# Schematic.net
KiCad netlist of a schematic drawn in EAGLE
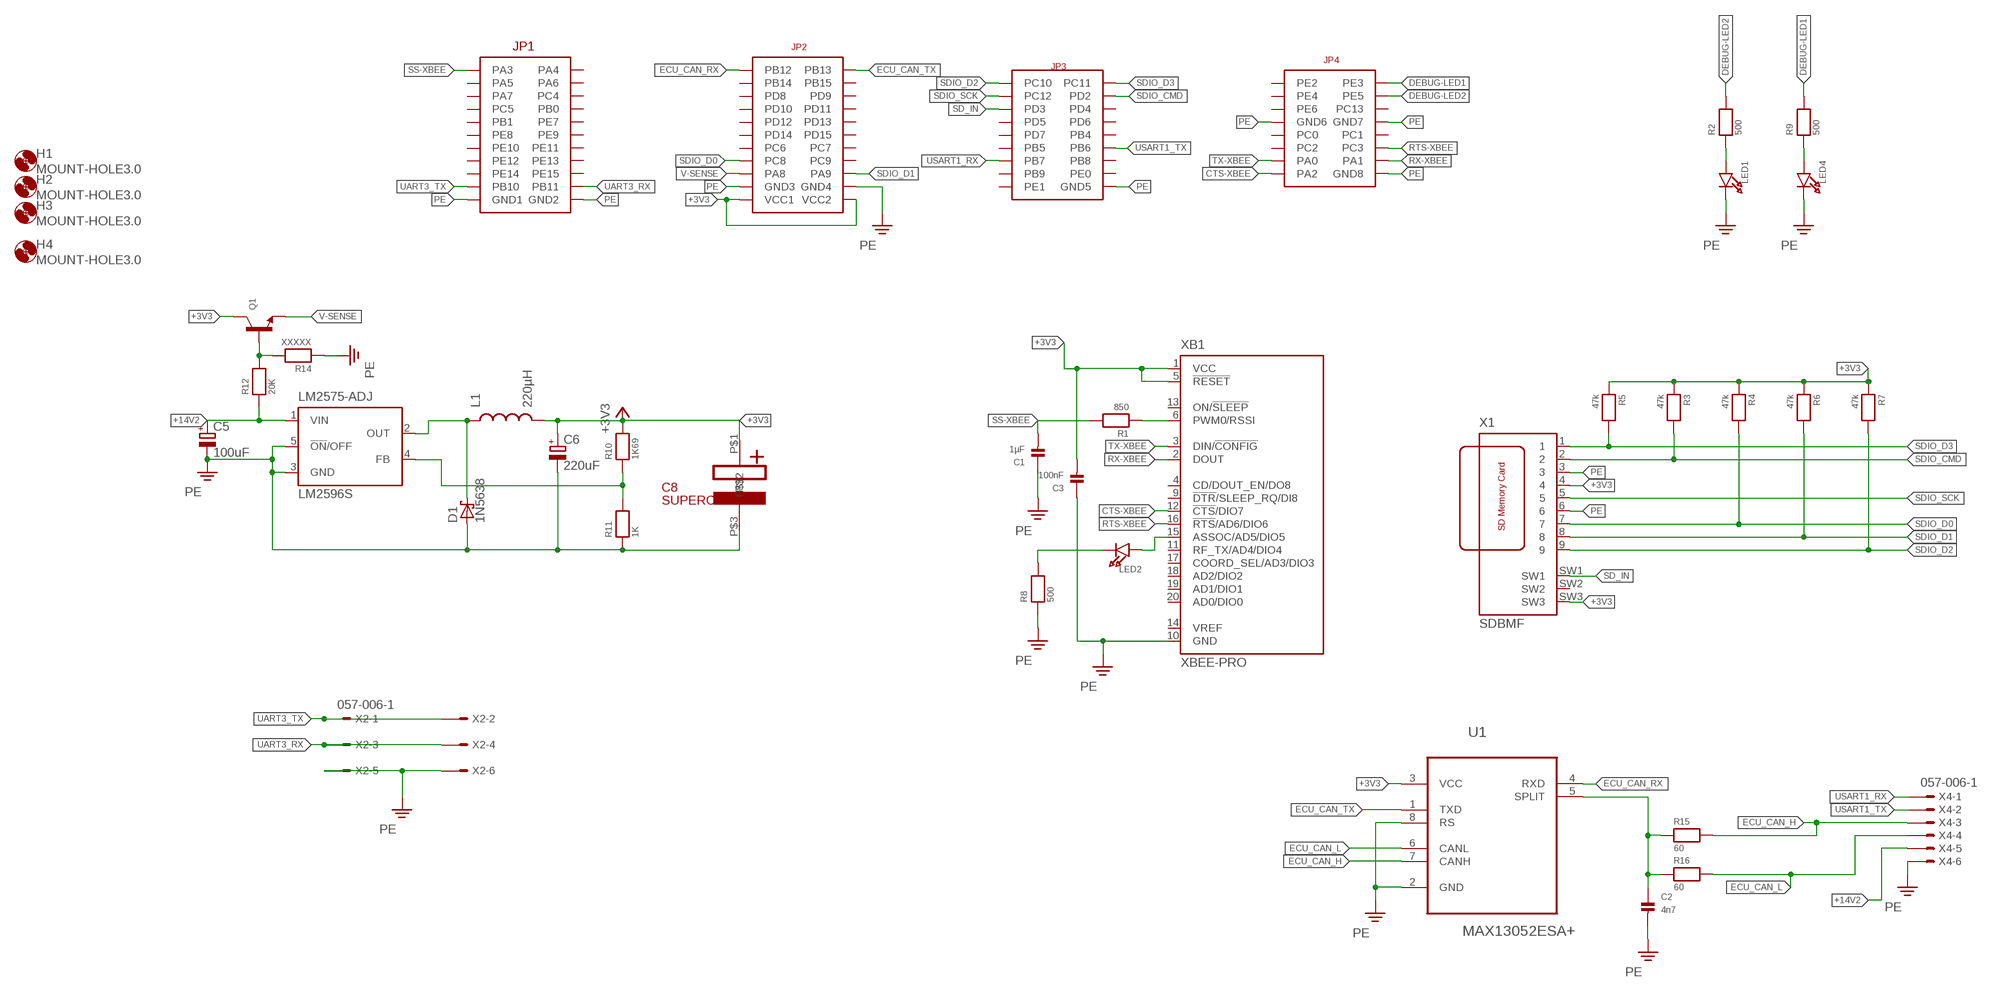
[diagram p0: schematic, sheet 1]

(export (version "E")
  (design (tool "Eeschema 10.0.6"))
  (components
    (comp (ref "C1")
      (value "1µF")
      (footprint "eagle-import:_0805")
      (libsource (lib "eagle-import") (part "CAP_CERAMIC_0805"))
    )
    (comp (ref "C2")
      (value "4n7")
      (footprint "eagle-import:0603")
      (libsource (lib "eagle-import") (part "CAP_CERAMIC0603"))
    )
    (comp (ref "C3")
      (value "100nF")
      (footprint "eagle-import:_0603")
      (libsource (lib "eagle-import") (part "CAP_CERAMIC_0603"))
    )
    (comp (ref "C5")
      (value "100uF")
      (footprint "eagle-import:E15-5")
      (libsource (lib "eagle-import") (part "CPOL-EUE15-5AXIAL"))
    )
    (comp (ref "C6")
      (value "220uF")
      (footprint "eagle-import:E15-5")
      (libsource (lib "eagle-import") (part "CPOL-EUE15-5AXIAL"))
    )
    (comp (ref "C8")
      (value "SUPERCAP")
      (footprint "eagle-import:SUPERCAP")
      (libsource (lib "eagle-import") (part "SUPERCAP"))
    )
    (comp (ref "D1")
      (value "1N5638")
      (footprint "eagle-import:DO13M")
      (libsource (lib "eagle-import") (part "1N5638"))
    )
    (comp (ref "H1")
      (value "MOUNT-HOLE3.0")
      (footprint "eagle-import:3,0")
      (libsource (lib "eagle-import") (part "MOUNT-HOLE3.0"))
    )
    (comp (ref "H2")
      (value "MOUNT-HOLE3.0")
      (footprint "eagle-import:3,0")
      (libsource (lib "eagle-import") (part "MOUNT-HOLE3.0"))
    )
    (comp (ref "H3")
      (value "MOUNT-HOLE3.0")
      (footprint "eagle-import:3,0")
      (libsource (lib "eagle-import") (part "MOUNT-HOLE3.0"))
    )
    (comp (ref "H4")
      (value "MOUNT-HOLE3.0")
      (footprint "eagle-import:3,0")
      (libsource (lib "eagle-import") (part "MOUNT-HOLE3.0"))
    )
    (comp (ref "L1")
      (value "220µH")
      (footprint "eagle-import:CDRH125")
      (libsource (lib "eagle-import") (part "INDUCTORPWR"))
    )
    (comp (ref "LED1")
      (value "LED1206")
      (footprint "eagle-import:CHIPLED_1206")
      (libsource (lib "eagle-import") (part "LED1206"))
    )
    (comp (ref "LED2")
      (value "LED1206")
      (footprint "eagle-import:CHIPLED_1206")
      (libsource (lib "eagle-import") (part "LED1206"))
    )
    (comp (ref "LED4")
      (value "LED1206")
      (footprint "eagle-import:CHIPLED_1206")
      (libsource (lib "eagle-import") (part "LED1206"))
    )
    (comp (ref "LM2575-ADJ")
      (value "LM2596S")
      (footprint "eagle-import:TO263-5")
      (fields (field (name "MF") "NATIONAL SEMICONDUCTOR") (field (name "MPN") "LM2596S-ADJ/NOPB"))
      (libsource (lib "eagle-import") (part "LM2596S"))
    )
    (comp (ref "Q1")
      (value "TRANSISTOR_NPNWIDE")
      (footprint "eagle-import:SOT23-WIDE")
      (libsource (lib "eagle-import") (part "TRANSISTOR_NPNWIDE"))
    )
    (comp (ref "R1")
      (value "850")
      (footprint "eagle-import:_0603")
      (libsource (lib "eagle-import") (part "RESISTOR_0603"))
    )
    (comp (ref "R2")
      (value "500")
      (footprint "eagle-import:_0603")
      (libsource (lib "eagle-import") (part "RESISTOR_0603"))
    )
    (comp (ref "R3")
      (value "47k")
      (footprint "eagle-import:_0603")
      (libsource (lib "eagle-import") (part "RESISTOR_0603"))
    )
    (comp (ref "R4")
      (value "47k")
      (footprint "eagle-import:_0603")
      (libsource (lib "eagle-import") (part "RESISTOR_0603"))
    )
    (comp (ref "R5")
      (value "47k")
      (footprint "eagle-import:_0603")
      (libsource (lib "eagle-import") (part "RESISTOR_0603"))
    )
    (comp (ref "R6")
      (value "47k")
      (footprint "eagle-import:_0603")
      (libsource (lib "eagle-import") (part "RESISTOR_0603"))
    )
    (comp (ref "R7")
      (value "47k")
      (footprint "eagle-import:_0603")
      (libsource (lib "eagle-import") (part "RESISTOR_0603"))
    )
    (comp (ref "R8")
      (value "500")
      (footprint "eagle-import:_0603")
      (libsource (lib "eagle-import") (part "RESISTOR_0603"))
    )
    (comp (ref "R9")
      (value "500")
      (footprint "eagle-import:_0603")
      (libsource (lib "eagle-import") (part "RESISTOR_0603"))
    )
    (comp (ref "R10")
      (value "1K69")
      (footprint "eagle-import:_0603")
      (libsource (lib "eagle-import") (part "RESISTOR_0603"))
    )
    (comp (ref "R11")
      (value "1K")
      (footprint "eagle-import:_0603")
      (libsource (lib "eagle-import") (part "RESISTOR_0603"))
    )
    (comp (ref "R12")
      (value "20K")
      (footprint "eagle-import:_0603")
      (libsource (lib "eagle-import") (part "RESISTOR_0603"))
    )
    (comp (ref "R14")
      (value "XXXXX")
      (footprint "eagle-import:_0603")
      (libsource (lib "eagle-import") (part "RESISTOR_0603"))
    )
    (comp (ref "R15")
      (value "60")
      (footprint "eagle-import:_0603")
      (libsource (lib "eagle-import") (part "RESISTOR_0603"))
    )
    (comp (ref "R16")
      (value "60")
      (footprint "eagle-import:_0603")
      (libsource (lib "eagle-import") (part "RESISTOR_0603"))
    )
    (comp (ref "U$1")
      (value "CPU-BOARD")
      (footprint "eagle-import:CPU-BOARD-JP1")
      (libsource (lib "eagle-import") (part "CPU-BOARD"))
    )
    (comp (ref "U1")
      (value "MAX13052ESA+")
      (footprint "eagle-import:SOIC127P600X175-8N")
      (libsource (lib "eagle-import") (part "MAX13052ESA+"))
    )
    (comp (ref "X1")
      (value "SDBMF")
      (footprint "eagle-import:SDBMF-009XXBXX2")
      (libsource (lib "eagle-import") (part "SDBMF"))
    )
    (comp (ref "X2")
      (value "057-006-1")
      (footprint "eagle-import:057-006-1")
      (libsource (lib "eagle-import") (part "057-006-1"))
    )
    (comp (ref "X4")
      (value "057-006-1")
      (footprint "eagle-import:057-006-1")
      (fields (field (name "OC_FARNELL") "unknown") (field (name "OC_NEWARK") "unknown"))
      (libsource (lib "eagle-import") (part "057-006-1"))
    )
    (comp (ref "XB1")
      (value "XBEE-PRO")
      (footprint "eagle-import:XBEE-PRO")
      (fields (field (name "MPN") "XBP24-AWI-001"))
      (libsource (lib "eagle-import") (part "XBEE-PRO"))
    )
  )
  (nets
    (net (code "1") (name "+3V3") (class "Default")
      (node (ref "C3") (pin "2") (pinfunction "P$2_2") (pintype "passive"))
      (node (ref "C6") (pin "+") (pinfunction "+_+") (pintype "passive"))
      (node (ref "C8") (pin "P$1") (pinfunction "P$1_P$1") (pintype "bidirectional"))
      (node (ref "L1") (pin "2") (pinfunction "2_2") (pintype "passive"))
      (node (ref "Q1") (pin "3") (pinfunction "C_3") (pintype "passive"))
      (node (ref "R10") (pin "2") (pinfunction "2_2") (pintype "passive"))
      (node (ref "R3") (pin "1") (pinfunction "1_1") (pintype "passive"))
      (node (ref "R4") (pin "1") (pinfunction "1_1") (pintype "passive"))
      (node (ref "R5") (pin "1") (pinfunction "1_1") (pintype "passive"))
      (node (ref "R6") (pin "1") (pinfunction "1_1") (pintype "passive"))
      (node (ref "R7") (pin "1") (pinfunction "1_1") (pintype "passive"))
      (node (ref "U$1") (pin "P$43") (pinfunction "VCC1_P$43") (pintype "bidirectional"))
      (node (ref "U$1") (pin "P$44") (pinfunction "VCC2_P$44") (pintype "bidirectional"))
      (node (ref "U1") (pin "3") (pinfunction "VCC_3") (pintype "power_in"))
      (node (ref "X1") (pin "4") (pinfunction "4_4") (pintype "passive"))
      (node (ref "X1") (pin "SW3") (pinfunction "SW3_SW3") (pintype "passive"))
      (node (ref "XB1") (pin "1") (pinfunction "VCC_1") (pintype "power_in"))
      (node (ref "XB1") (pin "5") (pinfunction "~{RESET}_5") (pintype "input"))
    )
    (net (code "2") (name "+14V2") (class "Default")
      (node (ref "C5") (pin "+") (pinfunction "+_+") (pintype "passive"))
      (node (ref "LM2575-ADJ") (pin "1") (pinfunction "VIN_1") (pintype "input"))
      (node (ref "R12") (pin "1") (pinfunction "1_1") (pintype "passive"))
      (node (ref "X4") (pin "5") (pinfunction "S_5") (pintype "passive"))
    )
    (net (code "3") (name "CTS-XBEE") (class "Default")
      (node (ref "U$1") (pin "P$77") (pinfunction "PA2_P$77") (pintype "bidirectional"))
      (node (ref "XB1") (pin "12") (pinfunction "~{CTS}/DIO7_12") (pintype "bidirectional"))
    )
    (net (code "4") (name "DEBUG-LED1") (class "Default")
      (node (ref "R9") (pin "2") (pinfunction "2_2") (pintype "passive"))
      (node (ref "U$1") (pin "P$64") (pinfunction "PE3_P$64") (pintype "bidirectional"))
    )
    (net (code "5") (name "DEBUG-LED2") (class "Default")
      (node (ref "R2") (pin "2") (pinfunction "2_2") (pintype "passive"))
      (node (ref "U$1") (pin "P$66") (pinfunction "PE5_P$66") (pintype "bidirectional"))
    )
    (net (code "6") (name "ECU_CAN_H") (class "Default")
      (node (ref "R15") (pin "2") (pinfunction "2_2") (pintype "passive"))
      (node (ref "U1") (pin "7") (pinfunction "CANH_7") (pintype "input"))
      (node (ref "X4") (pin "3") (pinfunction "S_3") (pintype "passive"))
    )
    (net (code "7") (name "ECU_CAN_L") (class "Default")
      (node (ref "R16") (pin "2") (pinfunction "2_2") (pintype "passive"))
      (node (ref "U1") (pin "6") (pinfunction "CANL_6") (pintype "input"))
      (node (ref "X4") (pin "4") (pinfunction "S_4") (pintype "passive"))
    )
    (net (code "8") (name "ECU_CAN_RX") (class "Default")
      (node (ref "U$1") (pin "P$23") (pinfunction "PB12_P$23") (pintype "bidirectional"))
      (node (ref "U1") (pin "4") (pinfunction "RXD_4") (pintype "output"))
    )
    (net (code "9") (name "ECU_CAN_TX") (class "Default")
      (node (ref "U$1") (pin "P$24") (pinfunction "PB13_P$24") (pintype "bidirectional"))
      (node (ref "U1") (pin "1") (pinfunction "TXD_1") (pintype "input"))
    )
    (net (code "10") (name "Net-(C2-P$1)") (class "Default")
      (node (ref "C2") (pin "1") (pinfunction "P$1_1") (pintype "passive"))
      (node (ref "R15") (pin "1") (pinfunction "1_1") (pintype "passive"))
      (node (ref "R16") (pin "1") (pinfunction "1_1") (pintype "passive"))
      (node (ref "U1") (pin "5") (pinfunction "SPLIT_5") (pintype "output"))
    )
    (net (code "11") (name "Net-(LED1-PadA)") (class "Default")
      (node (ref "LED1") (pin "A") (pinfunction "A_A") (pintype "passive"))
      (node (ref "R2") (pin "1") (pinfunction "1_1") (pintype "passive"))
    )
    (net (code "12") (name "Net-(LED2-PadC)") (class "Default")
      (node (ref "LED2") (pin "C") (pinfunction "C_C") (pintype "passive"))
      (node (ref "R8") (pin "2") (pinfunction "2_2") (pintype "passive"))
    )
    (net (code "13") (name "Net-(LED4-PadA)") (class "Default")
      (node (ref "LED4") (pin "A") (pinfunction "A_A") (pintype "passive"))
      (node (ref "R9") (pin "1") (pinfunction "1_1") (pintype "passive"))
    )
    (net (code "14") (name "Net-(LM2575-ADJ-FB)") (class "Default")
      (node (ref "LM2575-ADJ") (pin "4") (pinfunction "FB_4") (pintype "input"))
      (node (ref "R10") (pin "1") (pinfunction "1_1") (pintype "passive"))
      (node (ref "R11") (pin "2") (pinfunction "2_2") (pintype "passive"))
    )
    (net (code "15") (name "Net-(LM2575-ADJ-OUT)") (class "Default")
      (node (ref "D1") (pin "C") (pinfunction "C_C") (pintype "passive"))
      (node (ref "L1") (pin "1") (pinfunction "1_1") (pintype "passive"))
      (node (ref "LM2575-ADJ") (pin "2") (pinfunction "OUT_2") (pintype "output"))
    )
    (net (code "16") (name "Net-(Q1-B)") (class "Default")
      (node (ref "Q1") (pin "1") (pinfunction "B_1") (pintype "passive"))
      (node (ref "R12") (pin "2") (pinfunction "2_2") (pintype "passive"))
      (node (ref "R14") (pin "2") (pinfunction "2_2") (pintype "passive"))
    )
    (net (code "17") (name "Net-(XB1-ASSOC{slash}AD5{slash}DIO5)") (class "Default")
      (node (ref "LED2") (pin "A") (pinfunction "A_A") (pintype "passive"))
      (node (ref "XB1") (pin "15") (pinfunction "ASSOC/AD5/DIO5_15") (pintype "bidirectional"))
    )
    (net (code "18") (name "Net-(XB1-PWM0{slash}RSSI)") (class "Default")
      (node (ref "R1") (pin "1") (pinfunction "1_1") (pintype "passive"))
      (node (ref "XB1") (pin "6") (pinfunction "PWM0/RSSI_6") (pintype "output"))
    )
    (net (code "19") (name "PE") (class "Default")
      (node (ref "C1") (pin "1") (pinfunction "P$1_1") (pintype "passive"))
      (node (ref "C2") (pin "2") (pinfunction "P$2_2") (pintype "passive"))
      (node (ref "C3") (pin "1") (pinfunction "P$1_1") (pintype "passive"))
      (node (ref "C5") (pin "-") (pinfunction "-_-") (pintype "passive"))
      (node (ref "C6") (pin "-") (pinfunction "-_-") (pintype "passive"))
      (node (ref "C8") (pin "P$3") (pinfunction "P$2_P$3") (pintype "bidirectional"))
      (node (ref "D1") (pin "A") (pinfunction "A_A") (pintype "passive"))
      (node (ref "LED1") (pin "C") (pinfunction "C_C") (pintype "passive"))
      (node (ref "LED4") (pin "C") (pinfunction "C_C") (pintype "passive"))
      (node (ref "LM2575-ADJ") (pin "3") (pinfunction "GND_3") (pintype "power_in"))
      (node (ref "LM2575-ADJ") (pin "5") (pinfunction "~{ON}/OFF_5") (pintype "input"))
      (node (ref "R11") (pin "1") (pinfunction "1_1") (pintype "passive"))
      (node (ref "R14") (pin "1") (pinfunction "1_1") (pintype "passive"))
      (node (ref "R8") (pin "1") (pinfunction "1_1") (pintype "passive"))
      (node (ref "U$1") (pin "P$19") (pinfunction "GND1_P$19") (pintype "bidirectional"))
      (node (ref "U$1") (pin "P$20") (pinfunction "GND2_P$20") (pintype "bidirectional"))
      (node (ref "U$1") (pin "P$41") (pinfunction "GND3_P$41") (pintype "bidirectional"))
      (node (ref "U$1") (pin "P$42") (pinfunction "GND4_P$42") (pintype "bidirectional"))
      (node (ref "U$1") (pin "P$62") (pinfunction "GND5_P$62") (pintype "bidirectional"))
      (node (ref "U$1") (pin "P$69") (pinfunction "GND6_P$69") (pintype "bidirectional"))
      (node (ref "U$1") (pin "P$70") (pinfunction "GND7_P$70") (pintype "bidirectional"))
      (node (ref "U$1") (pin "P$78") (pinfunction "GND8_P$78") (pintype "bidirectional"))
      (node (ref "U1") (pin "2") (pinfunction "GND_2") (pintype "passive"))
      (node (ref "U1") (pin "8") (pinfunction "RS_8") (pintype "input"))
      (node (ref "X1") (pin "3") (pinfunction "3_3") (pintype "passive"))
      (node (ref "X1") (pin "6") (pinfunction "6_6") (pintype "passive"))
      (node (ref "X2") (pin "5") (pinfunction "S_5") (pintype "passive"))
      (node (ref "X2") (pin "6") (pinfunction "S_6") (pintype "passive"))
      (node (ref "X4") (pin "6") (pinfunction "S_6") (pintype "passive"))
      (node (ref "XB1") (pin "10") (pinfunction "GND_10") (pintype "power_in"))
    )
    (net (code "20") (name "RTS-XBEE") (class "Default")
      (node (ref "U$1") (pin "P$74") (pinfunction "PC3_P$74") (pintype "bidirectional"))
      (node (ref "XB1") (pin "16") (pinfunction "~{RTS}/AD6/DIO6_16") (pintype "bidirectional"))
    )
    (net (code "21") (name "RX-XBEE") (class "Default")
      (node (ref "U$1") (pin "P$76") (pinfunction "PA1_P$76") (pintype "bidirectional"))
      (node (ref "XB1") (pin "2") (pinfunction "DOUT_2") (pintype "output"))
    )
    (net (code "22") (name "SDIO_CMD") (class "Default")
      (node (ref "R3") (pin "2") (pinfunction "2_2") (pintype "passive"))
      (node (ref "U$1") (pin "P$48") (pinfunction "PD2_P$48") (pintype "bidirectional"))
      (node (ref "X1") (pin "2") (pinfunction "2_2") (pintype "passive"))
    )
    (net (code "23") (name "SDIO_D0") (class "Default")
      (node (ref "R4") (pin "2") (pinfunction "2_2") (pintype "passive"))
      (node (ref "U$1") (pin "P$37") (pinfunction "PC8_P$37") (pintype "bidirectional"))
      (node (ref "X1") (pin "7") (pinfunction "7_7") (pintype "passive"))
    )
    (net (code "24") (name "SDIO_D1") (class "Default")
      (node (ref "R6") (pin "2") (pinfunction "2_2") (pintype "passive"))
      (node (ref "U$1") (pin "P$40") (pinfunction "PA9_P$40") (pintype "bidirectional"))
      (node (ref "X1") (pin "8") (pinfunction "8_8") (pintype "passive"))
    )
    (net (code "25") (name "SDIO_D2") (class "Default")
      (node (ref "R7") (pin "2") (pinfunction "2_2") (pintype "passive"))
      (node (ref "U$1") (pin "P$45") (pinfunction "PC10_P$45") (pintype "bidirectional"))
      (node (ref "X1") (pin "9") (pinfunction "9_9") (pintype "passive"))
    )
    (net (code "26") (name "SDIO_D3") (class "Default")
      (node (ref "R5") (pin "2") (pinfunction "2_2") (pintype "passive"))
      (node (ref "U$1") (pin "P$46") (pinfunction "PC11_P$46") (pintype "bidirectional"))
      (node (ref "X1") (pin "1") (pinfunction "1_1") (pintype "passive"))
    )
    (net (code "27") (name "SDIO_SCK") (class "Default")
      (node (ref "U$1") (pin "P$47") (pinfunction "PC12_P$47") (pintype "bidirectional"))
      (node (ref "X1") (pin "5") (pinfunction "5_5") (pintype "passive"))
    )
    (net (code "28") (name "SD_IN") (class "Default")
      (node (ref "U$1") (pin "P$49") (pinfunction "PD3_P$49") (pintype "bidirectional"))
      (node (ref "X1") (pin "SW1") (pinfunction "SW1_SW1") (pintype "passive"))
    )
    (net (code "29") (name "SS-XBEE") (class "Default")
      (node (ref "C1") (pin "2") (pinfunction "P$2_2") (pintype "passive"))
      (node (ref "R1") (pin "2") (pinfunction "2_2") (pintype "passive"))
      (node (ref "U$1") (pin "P$1") (pinfunction "PA3_P$1") (pintype "bidirectional"))
    )
    (net (code "30") (name "TX-XBEE") (class "Default")
      (node (ref "U$1") (pin "P$75") (pinfunction "PA0_P$75") (pintype "bidirectional"))
      (node (ref "XB1") (pin "3") (pinfunction "DIN/~{CONFIG}_3") (pintype "input"))
    )
    (net (code "31") (name "UART3_RX") (class "Default")
      (node (ref "U$1") (pin "P$22") (pinfunction "PB11_P$22") (pintype "bidirectional"))
      (node (ref "X2") (pin "3") (pinfunction "S_3") (pintype "passive"))
      (node (ref "X2") (pin "4") (pinfunction "S_4") (pintype "passive"))
    )
    (net (code "32") (name "UART3_TX") (class "Default")
      (node (ref "U$1") (pin "P$21") (pinfunction "PB10_P$21") (pintype "bidirectional"))
      (node (ref "X2") (pin "1") (pinfunction "S_1") (pintype "passive"))
      (node (ref "X2") (pin "2") (pinfunction "S_2") (pintype "passive"))
    )
    (net (code "33") (name "USART1_RX") (class "Default")
      (node (ref "U$1") (pin "P$57") (pinfunction "PB7_P$57") (pintype "bidirectional"))
      (node (ref "X4") (pin "1") (pinfunction "S_1") (pintype "passive"))
    )
    (net (code "34") (name "USART1_TX") (class "Default")
      (node (ref "U$1") (pin "P$56") (pinfunction "PB6_P$56") (pintype "bidirectional"))
      (node (ref "X4") (pin "2") (pinfunction "S_2") (pintype "passive"))
    )
    (net (code "35") (name "V-SENSE") (class "Default")
      (node (ref "Q1") (pin "2") (pinfunction "E_2") (pintype "passive"))
      (node (ref "U$1") (pin "P$39") (pinfunction "PA8_P$39") (pintype "bidirectional"))
    )
    (net (code "36") (name "unconnected-(U$1A-PA4-PadP$2)") (class "Default")
      (node (ref "U$1") (pin "P$2") (pinfunction "PA4_P$2") (pintype "bidirectional"))
    )
    (net (code "37") (name "unconnected-(U$1A-PA5-PadP$3)") (class "Default")
      (node (ref "U$1") (pin "P$3") (pinfunction "PA5_P$3") (pintype "bidirectional"))
    )
    (net (code "38") (name "unconnected-(U$1A-PA6-PadP$4)") (class "Default")
      (node (ref "U$1") (pin "P$4") (pinfunction "PA6_P$4") (pintype "bidirectional"))
    )
    (net (code "39") (name "unconnected-(U$1A-PA7-PadP$5)") (class "Default")
      (node (ref "U$1") (pin "P$5") (pinfunction "PA7_P$5") (pintype "bidirectional"))
    )
    (net (code "40") (name "unconnected-(U$1A-PB0-PadP$8)") (class "Default")
      (node (ref "U$1") (pin "P$8") (pinfunction "PB0_P$8") (pintype "bidirectional"))
    )
    (net (code "41") (name "unconnected-(U$1A-PB1-PadP$9)") (class "Default")
      (node (ref "U$1") (pin "P$9") (pinfunction "PB1_P$9") (pintype "bidirectional"))
    )
    (net (code "42") (name "unconnected-(U$1A-PC4-PadP$6)") (class "Default")
      (node (ref "U$1") (pin "P$6") (pinfunction "PC4_P$6") (pintype "bidirectional"))
    )
    (net (code "43") (name "unconnected-(U$1A-PC5-PadP$7)") (class "Default")
      (node (ref "U$1") (pin "P$7") (pinfunction "PC5_P$7") (pintype "bidirectional"))
    )
    (net (code "44") (name "unconnected-(U$1A-PE7-PadP$10)") (class "Default")
      (node (ref "U$1") (pin "P$10") (pinfunction "PE7_P$10") (pintype "bidirectional"))
    )
    (net (code "45") (name "unconnected-(U$1A-PE8-PadP$11)") (class "Default")
      (node (ref "U$1") (pin "P$11") (pinfunction "PE8_P$11") (pintype "bidirectional"))
    )
    (net (code "46") (name "unconnected-(U$1A-PE9-PadP$12)") (class "Default")
      (node (ref "U$1") (pin "P$12") (pinfunction "PE9_P$12") (pintype "bidirectional"))
    )
    (net (code "47") (name "unconnected-(U$1A-PE10-PadP$13)") (class "Default")
      (node (ref "U$1") (pin "P$13") (pinfunction "PE10_P$13") (pintype "bidirectional"))
    )
    (net (code "48") (name "unconnected-(U$1A-PE11-PadP$14)") (class "Default")
      (node (ref "U$1") (pin "P$14") (pinfunction "PE11_P$14") (pintype "bidirectional"))
    )
    (net (code "49") (name "unconnected-(U$1A-PE12-PadP$15)") (class "Default")
      (node (ref "U$1") (pin "P$15") (pinfunction "PE12_P$15") (pintype "bidirectional"))
    )
    (net (code "50") (name "unconnected-(U$1A-PE13-PadP$16)") (class "Default")
      (node (ref "U$1") (pin "P$16") (pinfunction "PE13_P$16") (pintype "bidirectional"))
    )
    (net (code "51") (name "unconnected-(U$1A-PE14-PadP$17)") (class "Default")
      (node (ref "U$1") (pin "P$17") (pinfunction "PE14_P$17") (pintype "bidirectional"))
    )
    (net (code "52") (name "unconnected-(U$1A-PE15-PadP$18)") (class "Default")
      (node (ref "U$1") (pin "P$18") (pinfunction "PE15_P$18") (pintype "bidirectional"))
    )
    (net (code "53") (name "unconnected-(U$1B-PB14-PadP$25)") (class "Default")
      (node (ref "U$1") (pin "P$25") (pinfunction "PB14_P$25") (pintype "bidirectional"))
    )
    (net (code "54") (name "unconnected-(U$1B-PB15-PadP$26)") (class "Default")
      (node (ref "U$1") (pin "P$26") (pinfunction "PB15_P$26") (pintype "bidirectional"))
    )
    (net (code "55") (name "unconnected-(U$1B-PC6-PadP$35)") (class "Default")
      (node (ref "U$1") (pin "P$35") (pinfunction "PC6_P$35") (pintype "bidirectional"))
    )
    (net (code "56") (name "unconnected-(U$1B-PC7-PadP$36)") (class "Default")
      (node (ref "U$1") (pin "P$36") (pinfunction "PC7_P$36") (pintype "bidirectional"))
    )
    (net (code "57") (name "unconnected-(U$1B-PC9-PadP$38)") (class "Default")
      (node (ref "U$1") (pin "P$38") (pinfunction "PC9_P$38") (pintype "bidirectional"))
    )
    (net (code "58") (name "unconnected-(U$1B-PD8-PadP$27)") (class "Default")
      (node (ref "U$1") (pin "P$27") (pinfunction "PD8_P$27") (pintype "bidirectional"))
    )
    (net (code "59") (name "unconnected-(U$1B-PD9-PadP$28)") (class "Default")
      (node (ref "U$1") (pin "P$28") (pinfunction "PD9_P$28") (pintype "bidirectional"))
    )
    (net (code "60") (name "unconnected-(U$1B-PD10-PadP$29)") (class "Default")
      (node (ref "U$1") (pin "P$29") (pinfunction "PD10_P$29") (pintype "bidirectional"))
    )
    (net (code "61") (name "unconnected-(U$1B-PD11-PadP$30)") (class "Default")
      (node (ref "U$1") (pin "P$30") (pinfunction "PD11_P$30") (pintype "bidirectional"))
    )
    (net (code "62") (name "unconnected-(U$1B-PD12-PadP$31)") (class "Default")
      (node (ref "U$1") (pin "P$31") (pinfunction "PD12_P$31") (pintype "bidirectional"))
    )
    (net (code "63") (name "unconnected-(U$1B-PD13-PadP$32)") (class "Default")
      (node (ref "U$1") (pin "P$32") (pinfunction "PD13_P$32") (pintype "bidirectional"))
    )
    (net (code "64") (name "unconnected-(U$1B-PD14-PadP$33)") (class "Default")
      (node (ref "U$1") (pin "P$33") (pinfunction "PD14_P$33") (pintype "bidirectional"))
    )
    (net (code "65") (name "unconnected-(U$1B-PD15-PadP$34)") (class "Default")
      (node (ref "U$1") (pin "P$34") (pinfunction "PD15_P$34") (pintype "bidirectional"))
    )
    (net (code "66") (name "unconnected-(U$1C-PB4-PadP$54)") (class "Default")
      (node (ref "U$1") (pin "P$54") (pinfunction "PB4_P$54") (pintype "bidirectional"))
    )
    (net (code "67") (name "unconnected-(U$1C-PB5-PadP$55)") (class "Default")
      (node (ref "U$1") (pin "P$55") (pinfunction "PB5_P$55") (pintype "bidirectional"))
    )
    (net (code "68") (name "unconnected-(U$1C-PB8-PadP$58)") (class "Default")
      (node (ref "U$1") (pin "P$58") (pinfunction "PB8_P$58") (pintype "bidirectional"))
    )
    (net (code "69") (name "unconnected-(U$1C-PB9-PadP$59)") (class "Default")
      (node (ref "U$1") (pin "P$59") (pinfunction "PB9_P$59") (pintype "bidirectional"))
    )
    (net (code "70") (name "unconnected-(U$1C-PD4-PadP$50)") (class "Default")
      (node (ref "U$1") (pin "P$50") (pinfunction "PD4_P$50") (pintype "bidirectional"))
    )
    (net (code "71") (name "unconnected-(U$1C-PD5-PadP$51)") (class "Default")
      (node (ref "U$1") (pin "P$51") (pinfunction "PD5_P$51") (pintype "bidirectional"))
    )
    (net (code "72") (name "unconnected-(U$1C-PD6-PadP$52)") (class "Default")
      (node (ref "U$1") (pin "P$52") (pinfunction "PD6_P$52") (pintype "bidirectional"))
    )
    (net (code "73") (name "unconnected-(U$1C-PD7-PadP$53)") (class "Default")
      (node (ref "U$1") (pin "P$53") (pinfunction "PD7_P$53") (pintype "bidirectional"))
    )
    (net (code "74") (name "unconnected-(U$1C-PE0-PadP$60)") (class "Default")
      (node (ref "U$1") (pin "P$60") (pinfunction "PE0_P$60") (pintype "bidirectional"))
    )
    (net (code "75") (name "unconnected-(U$1C-PE1-PadP$61)") (class "Default")
      (node (ref "U$1") (pin "P$61") (pinfunction "PE1_P$61") (pintype "bidirectional"))
    )
    (net (code "76") (name "unconnected-(U$1D-PC0-PadP$71)") (class "Default")
      (node (ref "U$1") (pin "P$71") (pinfunction "PC0_P$71") (pintype "bidirectional"))
    )
    (net (code "77") (name "unconnected-(U$1D-PC1-PadP$72)") (class "Default")
      (node (ref "U$1") (pin "P$72") (pinfunction "PC1_P$72") (pintype "bidirectional"))
    )
    (net (code "78") (name "unconnected-(U$1D-PC2-PadP$73)") (class "Default")
      (node (ref "U$1") (pin "P$73") (pinfunction "PC2_P$73") (pintype "bidirectional"))
    )
    (net (code "79") (name "unconnected-(U$1D-PC13-PadP$68)") (class "Default")
      (node (ref "U$1") (pin "P$68") (pinfunction "PC13_P$68") (pintype "bidirectional"))
    )
    (net (code "80") (name "unconnected-(U$1D-PE2-PadP$63)") (class "Default")
      (node (ref "U$1") (pin "P$63") (pinfunction "PE2_P$63") (pintype "bidirectional"))
    )
    (net (code "81") (name "unconnected-(U$1D-PE4-PadP$65)") (class "Default")
      (node (ref "U$1") (pin "P$65") (pinfunction "PE4_P$65") (pintype "bidirectional"))
    )
    (net (code "82") (name "unconnected-(U$1D-PE6-PadP$67)") (class "Default")
      (node (ref "U$1") (pin "P$67") (pinfunction "PE6_P$67") (pintype "bidirectional"))
    )
    (net (code "83") (name "unconnected-(X1-PadSW2)") (class "Default")
      (node (ref "X1") (pin "SW2") (pinfunction "SW2_SW2") (pintype "passive"))
    )
    (net (code "84") (name "unconnected-(XB1-AD0{slash}DIO0-Pad20)") (class "Default")
      (node (ref "XB1") (pin "20") (pinfunction "AD0/DIO0_20") (pintype "bidirectional"))
    )
    (net (code "85") (name "unconnected-(XB1-AD1{slash}DIO1-Pad19)") (class "Default")
      (node (ref "XB1") (pin "19") (pinfunction "AD1/DIO1_19") (pintype "bidirectional"))
    )
    (net (code "86") (name "unconnected-(XB1-AD2{slash}DIO2-Pad18)") (class "Default")
      (node (ref "XB1") (pin "18") (pinfunction "AD2/DIO2_18") (pintype "bidirectional"))
    )
    (net (code "87") (name "unconnected-(XB1-CD{slash}DOUT_EN{slash}DO8-Pad4)") (class "Default")
      (node (ref "XB1") (pin "4") (pinfunction "CD/DOUT_EN/DO8_4") (pintype "output"))
    )
    (net (code "88") (name "unconnected-(XB1-COORD_SEL{slash}AD3{slash}DIO3-Pad17)") (class "Default")
      (node (ref "XB1") (pin "17") (pinfunction "COORD_SEL/AD3/DIO3_17") (pintype "bidirectional"))
    )
    (net (code "89") (name "unconnected-(XB1-ON{slash}~{SLEEP}-Pad13)") (class "Default")
      (node (ref "XB1") (pin "13") (pinfunction "ON/~{SLEEP}_13") (pintype "output"))
    )
    (net (code "90") (name "unconnected-(XB1-RF_TX{slash}AD4{slash}DIO4-Pad11)") (class "Default")
      (node (ref "XB1") (pin "11") (pinfunction "RF_TX/AD4/DIO4_11") (pintype "bidirectional"))
    )
    (net (code "91") (name "unconnected-(XB1-VREF-Pad14)") (class "Default")
      (node (ref "XB1") (pin "14") (pinfunction "VREF_14") (pintype "input"))
    )
    (net (code "92") (name "unconnected-(XB1-~{DTR}{slash}SLEEP_RQ{slash}DI8-Pad9)") (class "Default")
      (node (ref "XB1") (pin "9") (pinfunction "~{DTR}/SLEEP_RQ/DI8_9") (pintype "bidirectional"))
    )
  )
)
